# LiFeLight.net
KiCad netlist of a schematic drawn in EAGLE
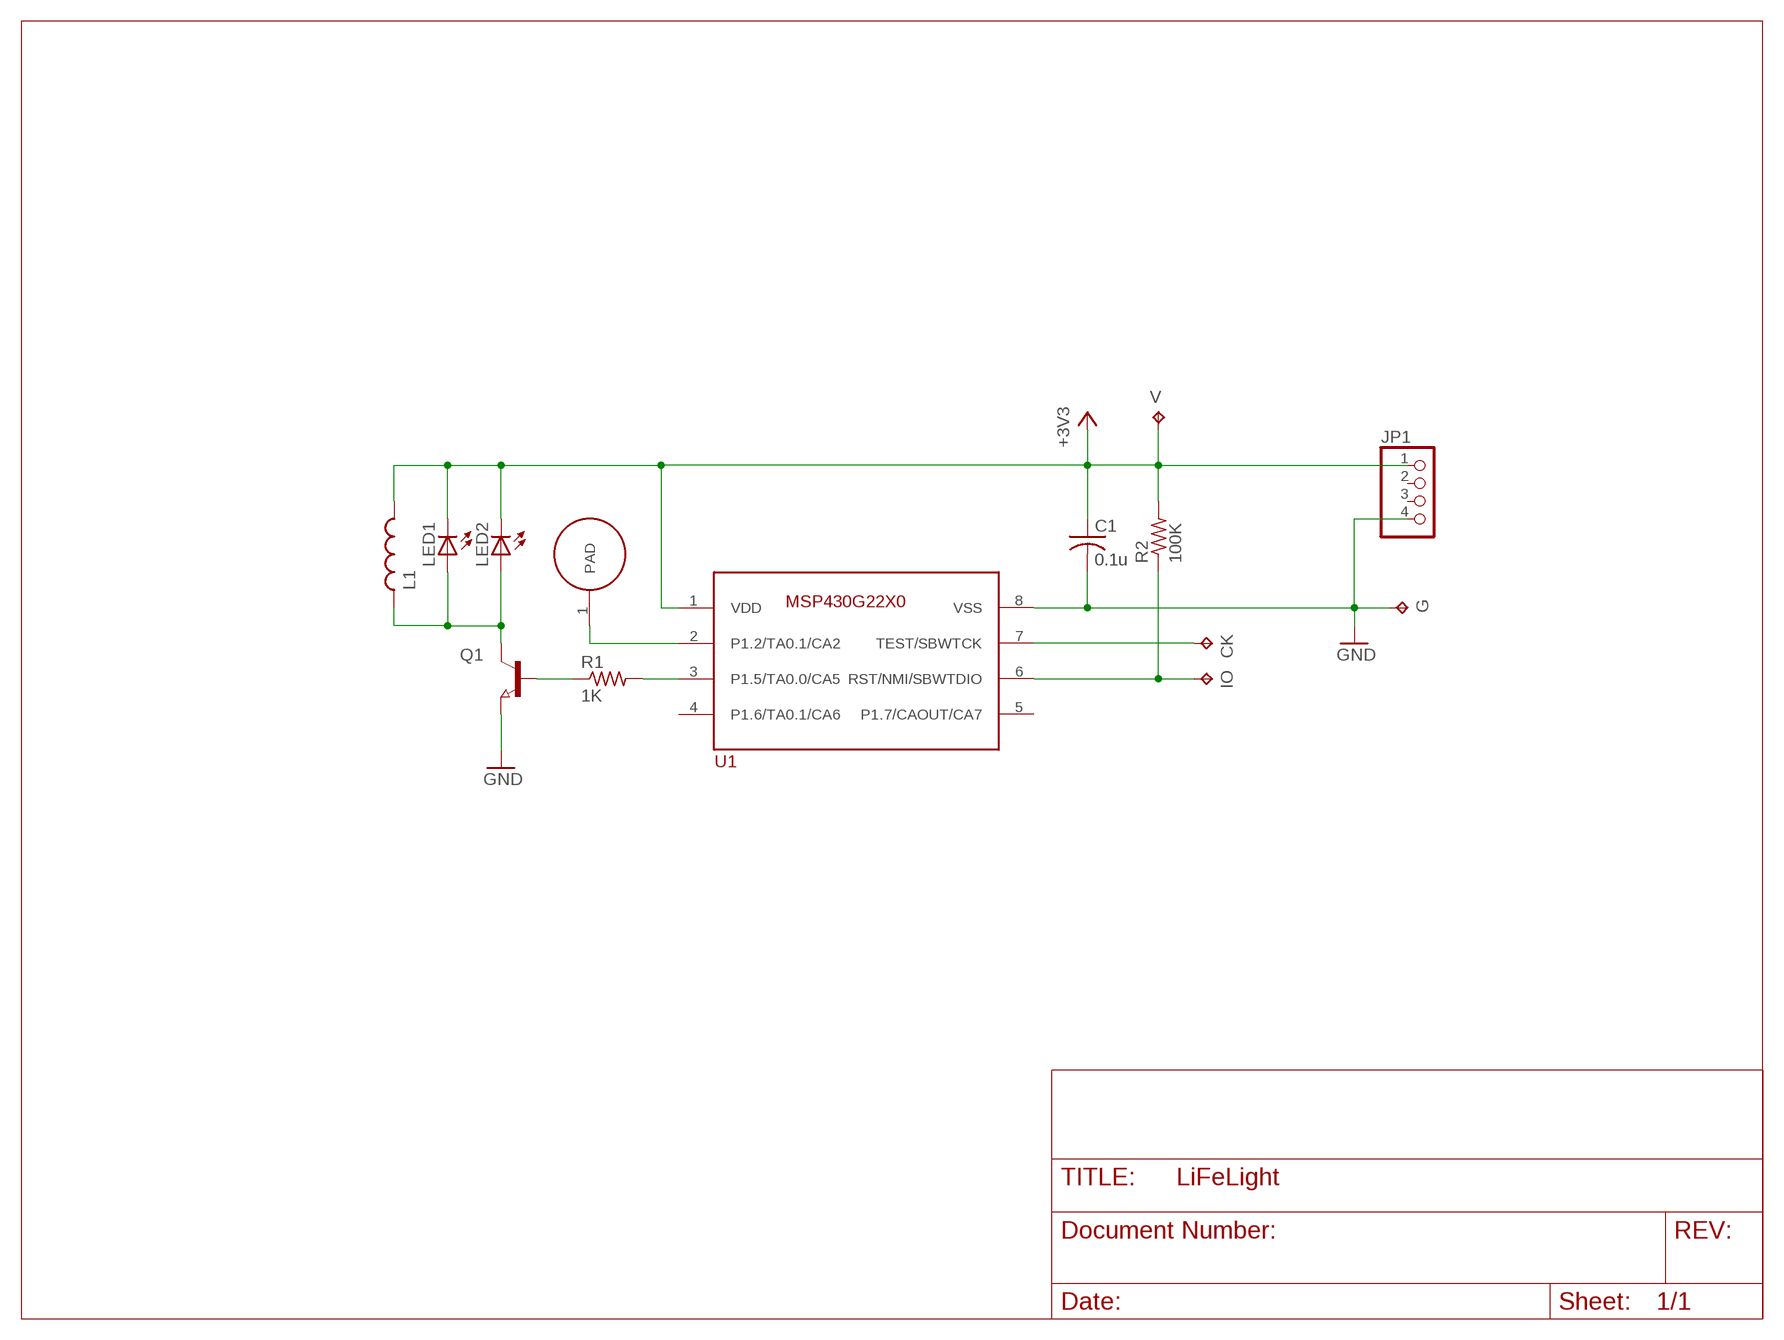
[diagram p0: schematic, sheet 1]

(export (version "E")
  (design (tool "Eeschema 10.0.6"))
  (components
    (comp (ref "C1")
      (value "0.1u")
      (footprint "eagle-import:C0805K")
      (libsource (lib "eagle-import") (part "C-USC0805K"))
    )
    (comp (ref "CK")
      (value "TPB1,27")
      (footprint "eagle-import:B1,27")
      (libsource (lib "eagle-import") (part "TPB1,27"))
    )
    (comp (ref "G")
      (value "TPB1,27")
      (footprint "eagle-import:B1,27")
      (libsource (lib "eagle-import") (part "TPB1,27"))
    )
    (comp (ref "IO")
      (value "TPB1,27")
      (footprint "eagle-import:B1,27")
      (libsource (lib "eagle-import") (part "TPB1,27"))
    )
    (comp (ref "JP1")
      (value "PINHD-1X4")
      (footprint "eagle-import:1X04")
      (libsource (lib "eagle-import") (part "PINHD-1X4"))
    )
    (comp (ref "L1")
      (value "L-USL2825P")
      (footprint "eagle-import:L2825P")
      (libsource (lib "eagle-import") (part "L-USL2825P"))
    )
    (comp (ref "LED1")
      (value "LEDSQR2X5")
      (footprint "eagle-import:LED2X5")
      (libsource (lib "eagle-import") (part "LEDSQR2X5"))
    )
    (comp (ref "LED2")
      (value "LEDSMT1206")
      (footprint "eagle-import:1206")
      (libsource (lib "eagle-import") (part "LEDSMT1206"))
    )
    (comp (ref "Q1")
      (value "NPN-TRANSISTOR_SOT23")
      (footprint "eagle-import:SOT23")
      (libsource (lib "eagle-import") (part "NPN-TRANSISTOR_SOT23"))
    )
    (comp (ref "R1")
      (value "1K")
      (footprint "eagle-import:R0805")
      (libsource (lib "eagle-import") (part "R-US_R0805"))
    )
    (comp (ref "R2")
      (value "100K")
      (footprint "eagle-import:R0805")
      (libsource (lib "eagle-import") (part "R-US_R0805"))
    )
    (comp (ref "TOUCH1")
      (value "TOUCHPAD8MM")
      (footprint "eagle-import:TOUCHPAD8")
      (libsource (lib "eagle-import") (part "TOUCHPAD8MM"))
    )
    (comp (ref "U1")
      (value "MSP430G22X0")
      (footprint "eagle-import:SO08")
      (libsource (lib "eagle-import") (part "MSP430G22X0"))
    )
    (comp (ref "V")
      (value "TPB1,27")
      (footprint "eagle-import:B1,27")
      (libsource (lib "eagle-import") (part "TPB1,27"))
    )
  )
  (nets
    (net (code "1") (name "+3V3") (class "Default")
      (node (ref "C1") (pin "1") (pinfunction "1_1") (pintype "passive"))
      (node (ref "JP1") (pin "1") (pinfunction "1_1") (pintype "passive"))
      (node (ref "L1") (pin "1") (pinfunction "1_1") (pintype "passive"))
      (node (ref "LED1") (pin "K") (pinfunction "C_K") (pintype "passive"))
      (node (ref "LED2") (pin "C") (pinfunction "C_C") (pintype "passive"))
      (node (ref "R2") (pin "2") (pinfunction "2_2") (pintype "passive"))
      (node (ref "U1") (pin "1") (pinfunction "VDD_1") (pintype "bidirectional"))
      (node (ref "V") (pin "TP") (pinfunction "TP_TP") (pintype "input"))
    )
    (net (code "2") (name "GND") (class "Default")
      (node (ref "C1") (pin "2") (pinfunction "2_2") (pintype "passive"))
      (node (ref "G") (pin "TP") (pinfunction "TP_TP") (pintype "input"))
      (node (ref "JP1") (pin "4") (pinfunction "4_4") (pintype "passive"))
      (node (ref "Q1") (pin "2") (pinfunction "E_2") (pintype "passive"))
      (node (ref "U1") (pin "8") (pinfunction "VSS_8") (pintype "bidirectional"))
    )
    (net (code "3") (name "Net-(Q1-B)") (class "Default")
      (node (ref "Q1") (pin "1") (pinfunction "B_1") (pintype "passive"))
      (node (ref "R1") (pin "1") (pinfunction "1_1") (pintype "passive"))
    )
    (net (code "4") (name "Net-(Q1-C)") (class "Default")
      (node (ref "L1") (pin "2") (pinfunction "2_2") (pintype "passive"))
      (node (ref "LED1") (pin "A") (pinfunction "A_A") (pintype "passive"))
      (node (ref "LED2") (pin "A") (pinfunction "A_A") (pintype "passive"))
      (node (ref "Q1") (pin "3") (pinfunction "C_3") (pintype "passive"))
    )
    (net (code "5") (name "Net-(TOUCH1-PAD)") (class "Default")
      (node (ref "TOUCH1") (pin "1") (pinfunction "PAD_1") (pintype "bidirectional"))
      (node (ref "U1") (pin "2") (pinfunction "P1.2/TA0.1/CA2_2") (pintype "bidirectional"))
    )
    (net (code "6") (name "Net-(U1-P1.5{slash}TA0.0{slash}CA5)") (class "Default")
      (node (ref "R1") (pin "2") (pinfunction "2_2") (pintype "passive"))
      (node (ref "U1") (pin "3") (pinfunction "P1.5/TA0.0/CA5_3") (pintype "bidirectional"))
    )
    (net (code "7") (name "Net-(U1-RST{slash}NMI{slash}SBWTDIO)") (class "Default")
      (node (ref "IO") (pin "TP") (pinfunction "TP_TP") (pintype "input"))
      (node (ref "R2") (pin "1") (pinfunction "1_1") (pintype "passive"))
      (node (ref "U1") (pin "6") (pinfunction "RST/NMI/SBWTDIO_6") (pintype "bidirectional"))
    )
    (net (code "8") (name "Net-(U1-TEST{slash}SBWTCK)") (class "Default")
      (node (ref "CK") (pin "TP") (pinfunction "TP_TP") (pintype "input"))
      (node (ref "U1") (pin "7") (pinfunction "TEST/SBWTCK_7") (pintype "bidirectional"))
    )
    (net (code "9") (name "unconnected-(JP1-Pad2)") (class "Default")
      (node (ref "JP1") (pin "2") (pinfunction "2_2") (pintype "passive"))
    )
    (net (code "10") (name "unconnected-(JP1-Pad3)") (class "Default")
      (node (ref "JP1") (pin "3") (pinfunction "3_3") (pintype "passive"))
    )
    (net (code "11") (name "unconnected-(U1-P1.6{slash}TA0.1{slash}CA6-Pad4)") (class "Default")
      (node (ref "U1") (pin "4") (pinfunction "P1.6/TA0.1/CA6_4") (pintype "bidirectional"))
    )
    (net (code "12") (name "unconnected-(U1-P1.7{slash}CAOUT{slash}CA7-Pad5)") (class "Default")
      (node (ref "U1") (pin "5") (pinfunction "P1.7/CAOUT/CA7_5") (pintype "bidirectional"))
    )
  )
)
